# DICO_giangrandi_v100.net
KiCad netlist of a schematic drawn in EAGLE
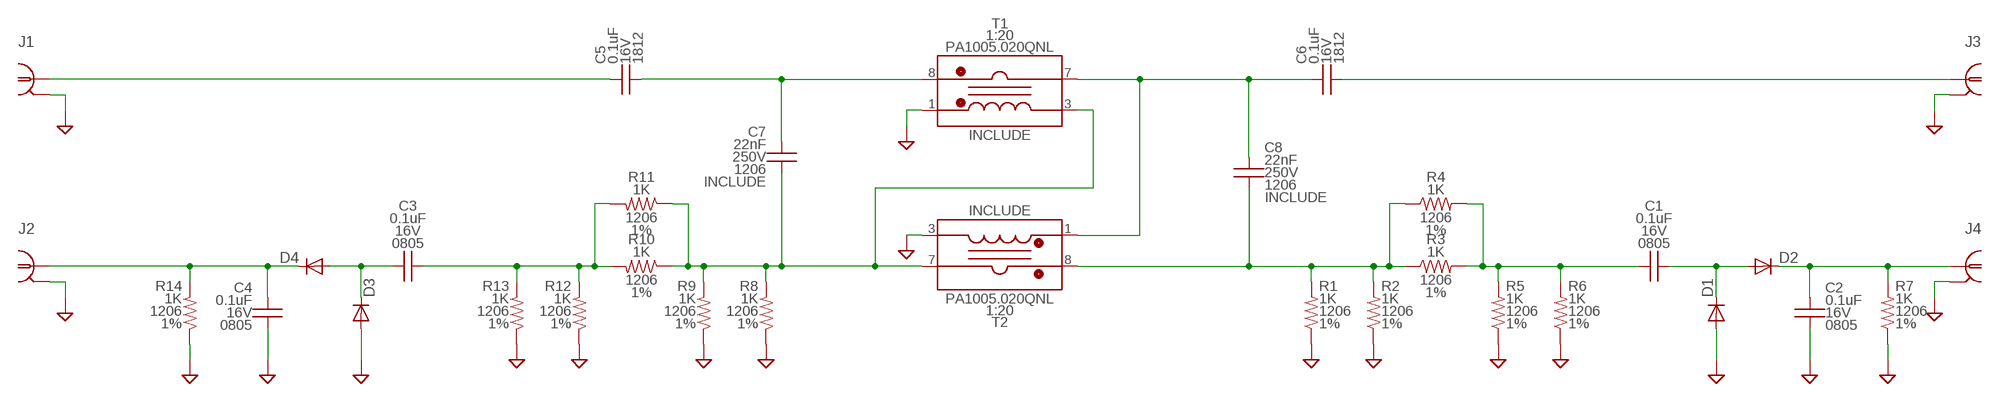
[diagram p0: schematic, sheet 1]

(export (version "E")
  (design (tool "Eeschema 10.0.6"))
  (components
    (comp (ref "C1")
      (value "0.1uF")
      (footprint "eagle-import:0805_IPC-7351B")
      (fields (field (name "PACKAGE") "0805") (field (name "VOLTAGE") "16V"))
      (libsource (lib "eagle-import") (part "C0805_IPCC-0.1U-16V-0805-X7R"))
    )
    (comp (ref "C2")
      (value "0.1uF")
      (footprint "eagle-import:0805_IPC-7351B")
      (fields (field (name "VOLTAGE") "16V"))
      (libsource (lib "eagle-import") (part "C0805_IPCC-0.1U-16V-0805-X7R"))
    )
    (comp (ref "C3")
      (value "0.1uF")
      (footprint "eagle-import:0805_IPC-7351B")
      (fields (field (name "PACKAGE") "0805") (field (name "VOLTAGE") "16V"))
      (libsource (lib "eagle-import") (part "C0805_IPCC-0.1U-16V-0805-X7R"))
    )
    (comp (ref "C4")
      (value "0.1uF")
      (footprint "eagle-import:0805_IPC-7351B")
      (fields (field (name "VOLTAGE") "16V"))
      (libsource (lib "eagle-import") (part "C0805_IPCC-0.1U-16V-0805-X7R"))
    )
    (comp (ref "C5")
      (value "0.1uF")
      (footprint "eagle-import:C1812")
      (fields (field (name "VOLTAGE") "16V"))
      (libsource (lib "eagle-import") (part "CC1812"))
    )
    (comp (ref "C6")
      (value "0.1uF")
      (footprint "eagle-import:C1812")
      (fields (field (name "VOLTAGE") "16V"))
      (libsource (lib "eagle-import") (part "CC1812"))
    )
    (comp (ref "C7")
      (value "22nF")
      (footprint "eagle-import:C1206")
      (fields (field (name "PARTNO") "C3216NP02E223J160AA") (field (name "VOLTAGE") "250V"))
      (libsource (lib "eagle-import") (part "CC1206C-22N-250V-5%-1206-NP0"))
    )
    (comp (ref "C8")
      (value "22nF")
      (footprint "eagle-import:C1206")
      (fields (field (name "PARTNO") "C3216NP02E223J160AA") (field (name "VOLTAGE") "250V"))
      (libsource (lib "eagle-import") (part "CC1206C-22N-250V-5%-1206-NP0"))
    )
    (comp (ref "D1")
      (value "DIODE-SOD123")
      (footprint "eagle-import:SOD123")
      (libsource (lib "eagle-import") (part "DIODE-SOD123"))
    )
    (comp (ref "D2")
      (value "DIODE-SOD123")
      (footprint "eagle-import:SOD123")
      (libsource (lib "eagle-import") (part "DIODE-SOD123"))
    )
    (comp (ref "D3")
      (value "DIODE-SOD123")
      (footprint "eagle-import:SOD123")
      (libsource (lib "eagle-import") (part "DIODE-SOD123"))
    )
    (comp (ref "D4")
      (value "DIODE-SOD123")
      (footprint "eagle-import:SOD123")
      (libsource (lib "eagle-import") (part "DIODE-SOD123"))
    )
    (comp (ref "J1")
      (value "COAXBNC_EDGE")
      (footprint "eagle-import:BNC_EDGE")
      (libsource (lib "eagle-import") (part "COAXBNC_EDGE"))
    )
    (comp (ref "J2")
      (value "COAXBNC_EDGE")
      (footprint "eagle-import:BNC_EDGE")
      (libsource (lib "eagle-import") (part "COAXBNC_EDGE"))
    )
    (comp (ref "J3")
      (value "COAXBNC_EDGE")
      (footprint "eagle-import:BNC_EDGE")
      (libsource (lib "eagle-import") (part "COAXBNC_EDGE"))
    )
    (comp (ref "J4")
      (value "COAXBNC_EDGE")
      (footprint "eagle-import:BNC_EDGE")
      (libsource (lib "eagle-import") (part "COAXBNC_EDGE"))
    )
    (comp (ref "R1")
      (value "1K")
      (footprint "eagle-import:R1206")
      (fields (field (name "POWER") "0.25"))
      (libsource (lib "eagle-import") (part "RR1206R-1.0K-1%-1206-0.25W"))
    )
    (comp (ref "R2")
      (value "1K")
      (footprint "eagle-import:R1206")
      (fields (field (name "POWER") "0.25"))
      (libsource (lib "eagle-import") (part "RR1206R-1.0K-1%-1206-0.25W"))
    )
    (comp (ref "R3")
      (value "1K")
      (footprint "eagle-import:R1206")
      (fields (field (name "POWER") "0.25"))
      (libsource (lib "eagle-import") (part "R90R1206R-1.0K-1%-1206-0.25W"))
    )
    (comp (ref "R4")
      (value "1K")
      (footprint "eagle-import:R1206")
      (fields (field (name "POWER") "0.25"))
      (libsource (lib "eagle-import") (part "R90R1206R-1.0K-1%-1206-0.25W"))
    )
    (comp (ref "R5")
      (value "1K")
      (footprint "eagle-import:R1206")
      (fields (field (name "POWER") "0.25"))
      (libsource (lib "eagle-import") (part "RR1206R-1.0K-1%-1206-0.25W"))
    )
    (comp (ref "R6")
      (value "1K")
      (footprint "eagle-import:R1206")
      (fields (field (name "POWER") "0.25"))
      (libsource (lib "eagle-import") (part "RR1206R-1.0K-1%-1206-0.25W"))
    )
    (comp (ref "R7")
      (value "1K")
      (footprint "eagle-import:R1206")
      (fields (field (name "POWER") "0.25"))
      (libsource (lib "eagle-import") (part "RR1206R-1.0K-1%-1206-0.25W"))
    )
    (comp (ref "R8")
      (value "1K")
      (footprint "eagle-import:R1206")
      (fields (field (name "POWER") "0.25"))
      (libsource (lib "eagle-import") (part "RR1206R-1.0K-1%-1206-0.25W"))
    )
    (comp (ref "R9")
      (value "1K")
      (footprint "eagle-import:R1206")
      (fields (field (name "POWER") "0.25"))
      (libsource (lib "eagle-import") (part "RR1206R-1.0K-1%-1206-0.25W"))
    )
    (comp (ref "R10")
      (value "1K")
      (footprint "eagle-import:R1206")
      (fields (field (name "POWER") "0.25"))
      (libsource (lib "eagle-import") (part "R90R1206R-1.0K-1%-1206-0.25W"))
    )
    (comp (ref "R11")
      (value "1K")
      (footprint "eagle-import:R1206")
      (fields (field (name "POWER") "0.25"))
      (libsource (lib "eagle-import") (part "R90R1206R-1.0K-1%-1206-0.25W"))
    )
    (comp (ref "R12")
      (value "1K")
      (footprint "eagle-import:R1206")
      (fields (field (name "POWER") "0.25"))
      (libsource (lib "eagle-import") (part "RR1206R-1.0K-1%-1206-0.25W"))
    )
    (comp (ref "R13")
      (value "1K")
      (footprint "eagle-import:R1206")
      (fields (field (name "POWER") "0.25"))
      (libsource (lib "eagle-import") (part "RR1206R-1.0K-1%-1206-0.25W"))
    )
    (comp (ref "R14")
      (value "1K")
      (footprint "eagle-import:R1206")
      (fields (field (name "POWER") "0.25"))
      (libsource (lib "eagle-import") (part "RR1206R-1.0K-1%-1206-0.25W"))
    )
    (comp (ref "T1")
      (value "TRAFO_CURRENTSENSEPA1005.020QNLPA1005")
      (footprint "eagle-import:PA1005")
      (fields (field (name "PARTNO") "PA1005.020QNL"))
      (libsource (lib "eagle-import") (part "TRAFO_CURRENTSENSEPA1005PA1005.020QNL"))
    )
    (comp (ref "T2")
      (value "TRAFO_CURRENTSENSEPA1005.020QNLPA1005")
      (footprint "eagle-import:PA1005")
      (fields (field (name "PARTNO") "PA1005.020QNL"))
      (libsource (lib "eagle-import") (part "TRAFO_CURRENTSENSEPA1005PA1005.020QNL"))
    )
  )
  (nets
    (net (code "1") (name "GND") (class "Default")
      (node (ref "C2") (pin "2") (pinfunction "2_2") (pintype "passive"))
      (node (ref "C4") (pin "2") (pinfunction "2_2") (pintype "passive"))
      (node (ref "D1") (pin "A") (pinfunction "A_A") (pintype "passive"))
      (node (ref "D3") (pin "A") (pinfunction "A_A") (pintype "passive"))
      (node (ref "J1") (pin "G1") (pinfunction "GND1_G1") (pintype "power_in"))
      (node (ref "J1") (pin "G2") (pinfunction "GND1_G2") (pintype "power_in"))
      (node (ref "J1") (pin "G3") (pinfunction "GND1_G3") (pintype "power_in"))
      (node (ref "J1") (pin "G4") (pinfunction "GND1_G4") (pintype "power_in"))
      (node (ref "J2") (pin "G1") (pinfunction "GND1_G1") (pintype "power_in"))
      (node (ref "J2") (pin "G2") (pinfunction "GND1_G2") (pintype "power_in"))
      (node (ref "J2") (pin "G3") (pinfunction "GND1_G3") (pintype "power_in"))
      (node (ref "J2") (pin "G4") (pinfunction "GND1_G4") (pintype "power_in"))
      (node (ref "J3") (pin "G1") (pinfunction "GND1_G1") (pintype "power_in"))
      (node (ref "J3") (pin "G2") (pinfunction "GND1_G2") (pintype "power_in"))
      (node (ref "J3") (pin "G3") (pinfunction "GND1_G3") (pintype "power_in"))
      (node (ref "J3") (pin "G4") (pinfunction "GND1_G4") (pintype "power_in"))
      (node (ref "J4") (pin "G1") (pinfunction "GND1_G1") (pintype "power_in"))
      (node (ref "J4") (pin "G2") (pinfunction "GND1_G2") (pintype "power_in"))
      (node (ref "J4") (pin "G3") (pinfunction "GND1_G3") (pintype "power_in"))
      (node (ref "J4") (pin "G4") (pinfunction "GND1_G4") (pintype "power_in"))
      (node (ref "R1") (pin "2") (pinfunction "2_2") (pintype "passive"))
      (node (ref "R12") (pin "2") (pinfunction "2_2") (pintype "passive"))
      (node (ref "R13") (pin "2") (pinfunction "2_2") (pintype "passive"))
      (node (ref "R14") (pin "2") (pinfunction "2_2") (pintype "passive"))
      (node (ref "R2") (pin "2") (pinfunction "2_2") (pintype "passive"))
      (node (ref "R5") (pin "2") (pinfunction "2_2") (pintype "passive"))
      (node (ref "R6") (pin "2") (pinfunction "2_2") (pintype "passive"))
      (node (ref "R7") (pin "2") (pinfunction "2_2") (pintype "passive"))
      (node (ref "R8") (pin "2") (pinfunction "2_2") (pintype "passive"))
      (node (ref "R9") (pin "2") (pinfunction "2_2") (pintype "passive"))
      (node (ref "T1") (pin "1") (pinfunction "SS_1") (pintype "passive"))
      (node (ref "T2") (pin "3") (pinfunction "SF_3") (pintype "passive"))
    )
    (net (code "2") (name "Net-(C1-Pad1)") (class "Default")
      (node (ref "C1") (pin "1") (pinfunction "1_1") (pintype "passive"))
      (node (ref "R3") (pin "2") (pinfunction "2_2") (pintype "passive"))
      (node (ref "R4") (pin "2") (pinfunction "2_2") (pintype "passive"))
      (node (ref "R5") (pin "1") (pinfunction "1_1") (pintype "passive"))
      (node (ref "R6") (pin "1") (pinfunction "1_1") (pintype "passive"))
    )
    (net (code "3") (name "Net-(C1-Pad2)") (class "Default")
      (node (ref "C1") (pin "2") (pinfunction "2_2") (pintype "passive"))
      (node (ref "D1") (pin "C") (pinfunction "C_C") (pintype "passive"))
      (node (ref "D2") (pin "A") (pinfunction "A_A") (pintype "passive"))
    )
    (net (code "4") (name "Net-(C3-Pad1)") (class "Default")
      (node (ref "C3") (pin "1") (pinfunction "1_1") (pintype "passive"))
      (node (ref "R10") (pin "2") (pinfunction "2_2") (pintype "passive"))
      (node (ref "R11") (pin "2") (pinfunction "2_2") (pintype "passive"))
      (node (ref "R12") (pin "1") (pinfunction "1_1") (pintype "passive"))
      (node (ref "R13") (pin "1") (pinfunction "1_1") (pintype "passive"))
    )
    (net (code "5") (name "Net-(C3-Pad2)") (class "Default")
      (node (ref "C3") (pin "2") (pinfunction "2_2") (pintype "passive"))
      (node (ref "D3") (pin "C") (pinfunction "C_C") (pintype "passive"))
      (node (ref "D4") (pin "A") (pinfunction "A_A") (pintype "passive"))
    )
    (net (code "6") (name "Net-(J1-1)") (class "Default")
      (node (ref "C5") (pin "1") (pinfunction "1_1") (pintype "passive"))
      (node (ref "J1") (pin "C") (pinfunction "1_C") (pintype "passive"))
    )
    (net (code "7") (name "Net-(J2-1)") (class "Default")
      (node (ref "C4") (pin "1") (pinfunction "1_1") (pintype "passive"))
      (node (ref "D4") (pin "C") (pinfunction "C_C") (pintype "passive"))
      (node (ref "J2") (pin "C") (pinfunction "1_C") (pintype "passive"))
      (node (ref "R14") (pin "1") (pinfunction "1_1") (pintype "passive"))
    )
    (net (code "8") (name "Net-(J3-1)") (class "Default")
      (node (ref "C6") (pin "2") (pinfunction "2_2") (pintype "passive"))
      (node (ref "J3") (pin "C") (pinfunction "1_C") (pintype "passive"))
    )
    (net (code "9") (name "Net-(J4-1)") (class "Default")
      (node (ref "C2") (pin "1") (pinfunction "1_1") (pintype "passive"))
      (node (ref "D2") (pin "C") (pinfunction "C_C") (pintype "passive"))
      (node (ref "J4") (pin "C") (pinfunction "1_C") (pintype "passive"))
      (node (ref "R7") (pin "1") (pinfunction "1_1") (pintype "passive"))
    )
    (net (code "10") (name "Net-(T1-PF)") (class "Default")
      (node (ref "C6") (pin "1") (pinfunction "1_1") (pintype "passive"))
      (node (ref "C8") (pin "1") (pinfunction "1_1") (pintype "passive"))
      (node (ref "T1") (pin "7") (pinfunction "PF_7") (pintype "passive"))
      (node (ref "T2") (pin "1") (pinfunction "SS_1") (pintype "passive"))
    )
    (net (code "11") (name "Net-(T1-PS)") (class "Default")
      (node (ref "C5") (pin "2") (pinfunction "2_2") (pintype "passive"))
      (node (ref "C7") (pin "1") (pinfunction "1_1") (pintype "passive"))
      (node (ref "T1") (pin "8") (pinfunction "PS_8") (pintype "passive"))
    )
    (net (code "12") (name "Net-(T1-SF)") (class "Default")
      (node (ref "C7") (pin "2") (pinfunction "2_2") (pintype "passive"))
      (node (ref "R10") (pin "1") (pinfunction "1_1") (pintype "passive"))
      (node (ref "R11") (pin "1") (pinfunction "1_1") (pintype "passive"))
      (node (ref "R8") (pin "1") (pinfunction "1_1") (pintype "passive"))
      (node (ref "R9") (pin "1") (pinfunction "1_1") (pintype "passive"))
      (node (ref "T1") (pin "3") (pinfunction "SF_3") (pintype "passive"))
      (node (ref "T2") (pin "7") (pinfunction "PF_7") (pintype "passive"))
    )
    (net (code "13") (name "Net-(T2-PS)") (class "Default")
      (node (ref "C8") (pin "2") (pinfunction "2_2") (pintype "passive"))
      (node (ref "R1") (pin "1") (pinfunction "1_1") (pintype "passive"))
      (node (ref "R2") (pin "1") (pinfunction "1_1") (pintype "passive"))
      (node (ref "R3") (pin "1") (pinfunction "1_1") (pintype "passive"))
      (node (ref "R4") (pin "1") (pinfunction "1_1") (pintype "passive"))
      (node (ref "T2") (pin "8") (pinfunction "PS_8") (pintype "passive"))
    )
  )
)
